# 11-LedDon.net
KiCad netlist of a schematic drawn in Altium Designer
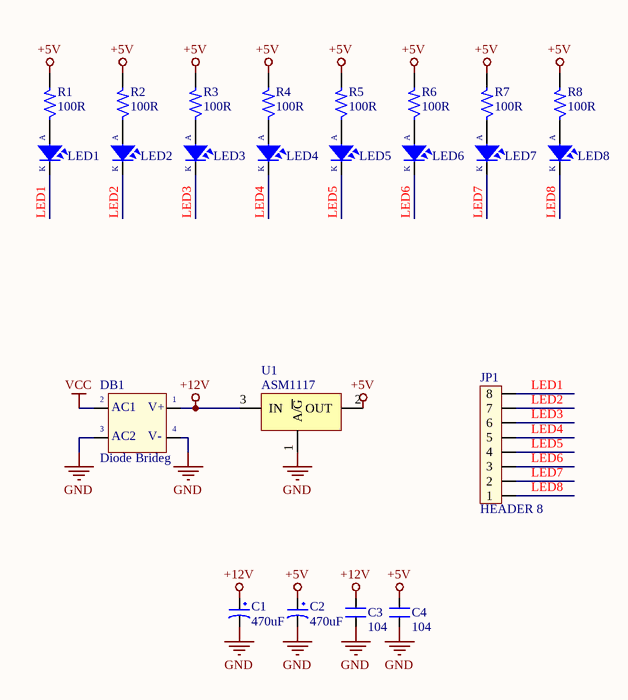
[diagram p0: 11-LedDon.SchDoc]

(export (version "E")
  (design (tool "Eeschema 10.0.6"))
  (components
    (comp (ref "C1")
      (value "470uF")
      (footprint "C-ALU-D6.5")
      (description "Cap P  0,1uF < 22uF , 16 - 50V")
      (libsource (lib "PART") (part "CP1"))
    )
    (comp (ref "C2")
      (value "470uF")
      (footprint "C-ALU-D6.5")
      (description "Cap P  0,1uF < 22uF , 16 - 50V")
      (libsource (lib "PART") (part "CP1"))
    )
    (comp (ref "C3")
      (value "104")
      (footprint "C-0805")
      (fields (field (name "DESIGNED BY") "VanDungEvn"))
      (libsource (lib "syhaunguyen") (part "CN"))
    )
    (comp (ref "C4")
      (value "104")
      (footprint "C-0805")
      (fields (field (name "DESIGNED BY") "VanDungEvn"))
      (libsource (lib "syhaunguyen") (part "CN"))
    )
    (comp (ref "DB1")
      (value "Diode Brideg")
      (footprint "D-DB-1A-SMD")
      (description "Convert AC to DC voltage, 4 pin")
      (libsource (lib "PART") (part "DB"))
    )
    (comp (ref "JP1")
      (value "HEADER 8")
      (footprint "JP8-2.54")
      (description "JP8 PIN")
      (libsource (lib "PART") (part "JP8"))
    )
    (comp (ref "LED1")
      (value "LED")
      (footprint "LED-D3")
      (description "LED Single colour Green and Red")
      (libsource (lib "PART") (part "LED"))
    )
    (comp (ref "LED2")
      (value "LED")
      (footprint "LED-D3")
      (description "LED Single colour Green and Red")
      (libsource (lib "PART") (part "LED"))
    )
    (comp (ref "LED3")
      (value "LED")
      (footprint "LED-D3")
      (description "LED Single colour Green and Red")
      (libsource (lib "PART") (part "LED"))
    )
    (comp (ref "LED4")
      (value "LED")
      (footprint "LED-D3")
      (description "LED Single colour Green and Red")
      (libsource (lib "PART") (part "LED"))
    )
    (comp (ref "LED5")
      (value "LED")
      (footprint "LED-D3")
      (description "LED Single colour Green and Red")
      (libsource (lib "PART") (part "LED"))
    )
    (comp (ref "LED6")
      (value "LED")
      (footprint "LED-D3")
      (description "LED Single colour Green and Red")
      (libsource (lib "PART") (part "LED"))
    )
    (comp (ref "LED7")
      (value "LED")
      (footprint "LED-D3")
      (description "LED Single colour Green and Red")
      (libsource (lib "PART") (part "LED"))
    )
    (comp (ref "LED8")
      (value "LED")
      (footprint "LED-D3")
      (description "LED Single colour Green and Red")
      (libsource (lib "PART") (part "LED"))
    )
    (comp (ref "R1")
      (value "100R")
      (footprint "R-0805")
      (description "Resistor 1/4W")
      (libsource (lib "PART") (part "R"))
    )
    (comp (ref "R2")
      (value "100R")
      (footprint "R-0805")
      (description "Resistor 1/4W")
      (libsource (lib "PART") (part "R"))
    )
    (comp (ref "R3")
      (value "100R")
      (footprint "R-0805")
      (description "Resistor 1/4W")
      (libsource (lib "PART") (part "R"))
    )
    (comp (ref "R4")
      (value "100R")
      (footprint "R-0805")
      (description "Resistor 1/4W")
      (libsource (lib "PART") (part "R"))
    )
    (comp (ref "R5")
      (value "100R")
      (footprint "R-0805")
      (description "Resistor 1/4W")
      (libsource (lib "PART") (part "R"))
    )
    (comp (ref "R6")
      (value "100R")
      (footprint "R-0805")
      (description "Resistor 1/4W")
      (libsource (lib "PART") (part "R"))
    )
    (comp (ref "R7")
      (value "100R")
      (footprint "R-0805")
      (description "Resistor 1/4W")
      (libsource (lib "PART") (part "R"))
    )
    (comp (ref "R8")
      (value "100R")
      (footprint "R-0805")
      (description "Resistor 1/4W")
      (libsource (lib "PART") (part "R"))
    )
    (comp (ref "U1")
      (value "ASM1117")
      (footprint "TO-252")
      (libsource (lib "doAnTotNghiep2017Lib") (part "ASM1117"))
    )
  )
  (nets
    (net (code "1") (name "+5V") (class "Default")
      (node (ref "C2") (pin "1") (pinfunction "1_1") (pintype "passive"))
      (node (ref "C4") (pin "2") (pinfunction "2_2") (pintype "passive"))
      (node (ref "R1") (pin "2") (pinfunction "2_2") (pintype "passive"))
      (node (ref "R2") (pin "2") (pinfunction "2_2") (pintype "passive"))
      (node (ref "R3") (pin "2") (pinfunction "2_2") (pintype "passive"))
      (node (ref "R4") (pin "2") (pinfunction "2_2") (pintype "passive"))
      (node (ref "R5") (pin "2") (pinfunction "2_2") (pintype "passive"))
      (node (ref "R6") (pin "2") (pinfunction "2_2") (pintype "passive"))
      (node (ref "R7") (pin "2") (pinfunction "2_2") (pintype "passive"))
      (node (ref "R8") (pin "2") (pinfunction "2_2") (pintype "passive"))
      (node (ref "U1") (pin "2") (pinfunction "OUT_2") (pintype "passive"))
    )
    (net (code "2") (name "+12V") (class "Default")
      (node (ref "C1") (pin "1") (pinfunction "1_1") (pintype "passive"))
      (node (ref "C3") (pin "2") (pinfunction "2_2") (pintype "passive"))
      (node (ref "DB1") (pin "3") (pinfunction "AC2_3") (pintype "passive"))
      (node (ref "U1") (pin "3") (pinfunction "IN_3") (pintype "passive"))
    )
    (net (code "3") (name "/LED1") (class "Default")
      (node (ref "JP1") (pin "8") (pinfunction "8_8") (pintype "passive"))
      (node (ref "LED1") (pin "2") (pinfunction "K_2") (pintype "passive"))
    )
    (net (code "4") (name "/LED2") (class "Default")
      (node (ref "JP1") (pin "7") (pinfunction "7_7") (pintype "passive"))
      (node (ref "LED2") (pin "2") (pinfunction "K_2") (pintype "passive"))
    )
    (net (code "5") (name "/LED3") (class "Default")
      (node (ref "JP1") (pin "6") (pinfunction "6_6") (pintype "passive"))
      (node (ref "LED3") (pin "2") (pinfunction "K_2") (pintype "passive"))
    )
    (net (code "6") (name "/LED4") (class "Default")
      (node (ref "JP1") (pin "5") (pinfunction "5_5") (pintype "passive"))
      (node (ref "LED4") (pin "2") (pinfunction "K_2") (pintype "passive"))
    )
    (net (code "7") (name "/LED5") (class "Default")
      (node (ref "JP1") (pin "4") (pinfunction "4_4") (pintype "passive"))
      (node (ref "LED5") (pin "2") (pinfunction "K_2") (pintype "passive"))
    )
    (net (code "8") (name "/LED6") (class "Default")
      (node (ref "JP1") (pin "3") (pinfunction "3_3") (pintype "passive"))
      (node (ref "LED6") (pin "2") (pinfunction "K_2") (pintype "passive"))
    )
    (net (code "9") (name "/LED7") (class "Default")
      (node (ref "JP1") (pin "2") (pinfunction "2_2") (pintype "passive"))
      (node (ref "LED7") (pin "2") (pinfunction "K_2") (pintype "passive"))
    )
    (net (code "10") (name "/LED8") (class "Default")
      (node (ref "JP1") (pin "1") (pinfunction "1_1") (pintype "passive"))
      (node (ref "LED8") (pin "2") (pinfunction "K_2") (pintype "passive"))
    )
    (net (code "11") (name "GND") (class "Default")
      (node (ref "C1") (pin "2") (pinfunction "2_2") (pintype "passive"))
      (node (ref "C2") (pin "2") (pinfunction "2_2") (pintype "passive"))
      (node (ref "C3") (pin "1") (pinfunction "1_1") (pintype "passive"))
      (node (ref "C4") (pin "1") (pinfunction "1_1") (pintype "passive"))
      (node (ref "DB1") (pin "1") (pinfunction "+V_OUT_1") (pintype "passive"))
      (node (ref "DB1") (pin "4") (pinfunction "-V_OUT_4") (pintype "passive"))
      (node (ref "U1") (pin "1") (pinfunction "A/~{G}_1") (pintype "passive"))
    )
    (net (code "12") (name "Net-(LED1-A)") (class "Default")
      (node (ref "LED1") (pin "1") (pinfunction "A_1") (pintype "passive"))
      (node (ref "R1") (pin "1") (pinfunction "1_1") (pintype "passive"))
    )
    (net (code "13") (name "Net-(LED2-A)") (class "Default")
      (node (ref "LED2") (pin "1") (pinfunction "A_1") (pintype "passive"))
      (node (ref "R2") (pin "1") (pinfunction "1_1") (pintype "passive"))
    )
    (net (code "14") (name "Net-(LED3-A)") (class "Default")
      (node (ref "LED3") (pin "1") (pinfunction "A_1") (pintype "passive"))
      (node (ref "R3") (pin "1") (pinfunction "1_1") (pintype "passive"))
    )
    (net (code "15") (name "Net-(LED4-A)") (class "Default")
      (node (ref "LED4") (pin "1") (pinfunction "A_1") (pintype "passive"))
      (node (ref "R4") (pin "1") (pinfunction "1_1") (pintype "passive"))
    )
    (net (code "16") (name "Net-(LED5-A)") (class "Default")
      (node (ref "LED5") (pin "1") (pinfunction "A_1") (pintype "passive"))
      (node (ref "R5") (pin "1") (pinfunction "1_1") (pintype "passive"))
    )
    (net (code "17") (name "Net-(LED6-A)") (class "Default")
      (node (ref "LED6") (pin "1") (pinfunction "A_1") (pintype "passive"))
      (node (ref "R6") (pin "1") (pinfunction "1_1") (pintype "passive"))
    )
    (net (code "18") (name "Net-(LED7-A)") (class "Default")
      (node (ref "LED7") (pin "1") (pinfunction "A_1") (pintype "passive"))
      (node (ref "R7") (pin "1") (pinfunction "1_1") (pintype "passive"))
    )
    (net (code "19") (name "Net-(LED8-A)") (class "Default")
      (node (ref "LED8") (pin "1") (pinfunction "A_1") (pintype "passive"))
      (node (ref "R8") (pin "1") (pinfunction "1_1") (pintype "passive"))
    )
    (net (code "20") (name "VCC") (class "Default")
      (node (ref "DB1") (pin "2") (pinfunction "AC1_2") (pintype "passive"))
    )
  )
)
